# 14-I225-Main.net
KiCad netlist of a schematic drawn in Altium Designer
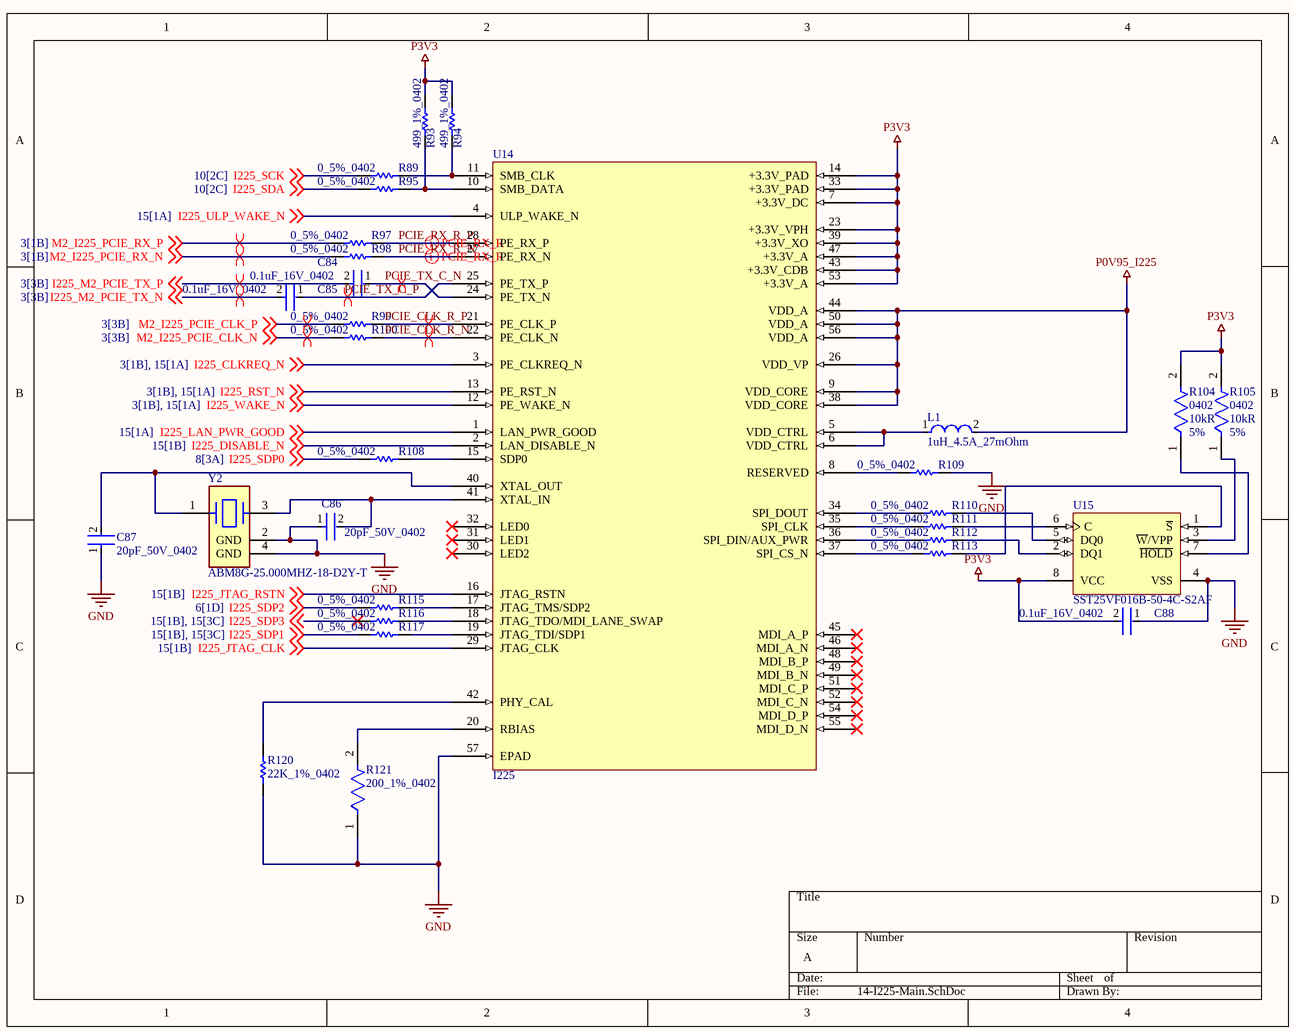
[diagram p0: 14-I225-Main.SchDoc]

(export (version "E")
  (design (tool "Eeschema 10.0.6"))
  (components
    (comp (ref "C84")
      (value "0.1uF_16V_0402")
      (footprint "FP-GRM15-MFG")
      (description "CAP CER 0.1UF 16V X7R 0402")
      (fields (field (name "MANUFACTURER PART NUMBER") "GRM155R71C104KA88D") (field (name "TOLERANCE") "10%"))
      (libsource (lib "Altium Content Vault") (part "236180d848d6139a670b325ea6854c9"))
    )
    (comp (ref "C85")
      (value "0.1uF_16V_0402")
      (footprint "FP-GRM15-MFG")
      (description "CAP CER 0.1UF 16V X7R 0402")
      (fields (field (name "MANUFACTURER PART NUMBER") "GRM155R71C104KA88D") (field (name "TOLERANCE") "10%"))
      (libsource (lib "Altium Content Vault") (part "236180d848d6139a670b325ea6854c9"))
    )
    (comp (ref "C86")
      (value "20pF_50V_0402")
      (footprint "FP-C0402-BB-MFG")
      (description "CAP CER 20PF 50V 5% NP0 0402")
      (fields
        (field (name "MANUFACTURER PART NUMBER") "C0402C200J5GACTU")
        (field (name "OCTOPART") "https://octopart.com/c0402c200j5gactu-kemet-9143900")
      )
      (libsource (lib "Altium Content Vault") (part "b4654b650e69147ec39a6b967a45e02"))
    )
    (comp (ref "C87")
      (value "20pF_50V_0402")
      (footprint "FP-C0402-BB-MFG")
      (description "CAP CER 20PF 50V 5% NP0 0402")
      (fields
        (field (name "MANUFACTURER PART NUMBER") "C0402C200J5GACTU")
        (field (name "OCTOPART") "https://octopart.com/c0402c200j5gactu-kemet-9143900")
      )
      (libsource (lib "Altium Content Vault") (part "b4654b650e69147ec39a6b967a45e02"))
    )
    (comp (ref "C88")
      (value "0.1uF_16V_0402")
      (footprint "FP-GRM15-MFG")
      (description "CAP CER 0.1UF 16V X7R 0402")
      (fields (field (name "MANUFACTURER PART NUMBER") "GRM155R71C104KA88D") (field (name "TOLERANCE") "10%"))
      (libsource (lib "Altium Content Vault") (part "236180d848d6139a670b325ea6854c9"))
    )
    (comp (ref "L1")
      (value "1uH_4.5A_27mOhm")
      (footprint "FP-IHLP-1616BZ-FP_1_8545x-MFG")
      (description "Fixed Inductors Commercial Low DCR Series SMT 1uH 4.5A 27mΩ 20%")
      (fields (field (name "TOLERANCE") "20%"))
      (libsource (lib "Altium Content Vault") (part "725321dda6339637d4d059423bc1c3c"))
    )
    (comp (ref "R89")
      (value "0_5%_0402")
      (footprint "RESC1005X40X25LL10T10")
      (fields (field (name "MANUFACTURER") "KOA Speer") (field (name "PART NUMBER") "RK73Z1ETTP"))
      (libsource (lib "Altium Content Vault") (part "RES"))
    )
    (comp (ref "R93")
      (value "499_1%_0402")
      (footprint "RESC1005X40X25LL05T05")
      (fields (field (name "MANUFACTURER") "Panasonic") (field (name "PART NUMBER") "ERJ-2RKF4990X"))
      (libsource (lib "Altium Content Vault") (part "RES"))
    )
    (comp (ref "R94")
      (value "499_1%_0402")
      (footprint "RESC1005X40X25LL05T05")
      (fields (field (name "MANUFACTURER") "Panasonic") (field (name "PART NUMBER") "ERJ-2RKF4990X"))
      (libsource (lib "Altium Content Vault") (part "RES"))
    )
    (comp (ref "R95")
      (value "0_5%_0402")
      (footprint "RESC1005X40X25LL10T10")
      (fields (field (name "MANUFACTURER") "KOA Speer") (field (name "PART NUMBER") "RK73Z1ETTP"))
      (libsource (lib "Altium Content Vault") (part "RES"))
    )
    (comp (ref "R97")
      (value "0_5%_0402")
      (footprint "RESC1005X40X25LL10T10")
      (fields (field (name "MANUFACTURER") "KOA Speer") (field (name "PART NUMBER") "RK73Z1ETTP"))
      (libsource (lib "Altium Content Vault") (part "RES"))
    )
    (comp (ref "R98")
      (value "0_5%_0402")
      (footprint "RESC1005X40X25LL10T10")
      (fields (field (name "MANUFACTURER") "KOA Speer") (field (name "PART NUMBER") "RK73Z1ETTP"))
      (libsource (lib "Altium Content Vault") (part "RES"))
    )
    (comp (ref "R99")
      (value "0_5%_0402")
      (footprint "RESC1005X40X25LL10T10")
      (fields (field (name "MANUFACTURER") "KOA Speer") (field (name "PART NUMBER") "RK73Z1ETTP"))
      (libsource (lib "Altium Content Vault") (part "RES"))
    )
    (comp (ref "R100")
      (value "0_5%_0402")
      (footprint "RESC1005X40X25LL10T10")
      (fields (field (name "MANUFACTURER") "KOA Speer") (field (name "PART NUMBER") "RK73Z1ETTP"))
      (libsource (lib "Altium Content Vault") (part "RES"))
    )
    (comp (ref "R104")
      (value "CRCW040210K0JNED")
      (footprint "FP-CRCW0402-e3-IPC_B")
      (description "RES Thick Film, 10kΩ, 5%, 0.063W, 200ppm/°C, 0402")
      (fields
        (field (name "CASE/PACKAGE") "0402")
        (field (name "RESISTANCE") "10kR")
        (field (name "TOLERANCE") "5%")
      )
      (libsource (lib "Altium Content Vault") (part "1029c3af85768c4190bb7ad29bc67b5"))
    )
    (comp (ref "R105")
      (value "CRCW040210K0JNED")
      (footprint "FP-CRCW0402-e3-IPC_B")
      (description "RES Thick Film, 10kΩ, 5%, 0.063W, 200ppm/°C, 0402")
      (fields
        (field (name "CASE/PACKAGE") "0402")
        (field (name "RESISTANCE") "10kR")
        (field (name "TOLERANCE") "5%")
      )
      (libsource (lib "Altium Content Vault") (part "1029c3af85768c4190bb7ad29bc67b5"))
    )
    (comp (ref "R108")
      (value "0_5%_0402")
      (footprint "RESC1005X40X25LL10T10")
      (fields (field (name "MANUFACTURER") "KOA Speer") (field (name "PART NUMBER") "RK73Z1ETTP"))
      (libsource (lib "Altium Content Vault") (part "RES"))
    )
    (comp (ref "R109")
      (value "0_5%_0402")
      (footprint "RESC1005X40X25LL10T10")
      (fields (field (name "MANUFACTURER") "KOA Speer") (field (name "PART NUMBER") "RK73Z1ETTP"))
      (libsource (lib "Altium Content Vault") (part "RES"))
    )
    (comp (ref "R110")
      (value "0_5%_0402")
      (footprint "RESC1005X40X25LL10T10")
      (fields (field (name "MANUFACTURER") "KOA Speer") (field (name "PART NUMBER") "RK73Z1ETTP"))
      (libsource (lib "Altium Content Vault") (part "RES"))
    )
    (comp (ref "R111")
      (value "0_5%_0402")
      (footprint "RESC1005X40X25LL10T10")
      (fields (field (name "MANUFACTURER") "KOA Speer") (field (name "PART NUMBER") "RK73Z1ETTP"))
      (libsource (lib "Altium Content Vault") (part "RES"))
    )
    (comp (ref "R112")
      (value "0_5%_0402")
      (footprint "RESC1005X40X25LL10T10")
      (fields (field (name "MANUFACTURER") "KOA Speer") (field (name "PART NUMBER") "RK73Z1ETTP"))
      (libsource (lib "Altium Content Vault") (part "RES"))
    )
    (comp (ref "R113")
      (value "0_5%_0402")
      (footprint "RESC1005X40X25LL10T10")
      (fields (field (name "MANUFACTURER") "KOA Speer") (field (name "PART NUMBER") "RK73Z1ETTP"))
      (libsource (lib "Altium Content Vault") (part "RES"))
    )
    (comp (ref "R115")
      (value "0_5%_0402")
      (footprint "RESC1005X40X25LL10T10")
      (fields (field (name "MANUFACTURER") "KOA Speer") (field (name "PART NUMBER") "RK73Z1ETTP"))
      (libsource (lib "Altium Content Vault") (part "RES"))
    )
    (comp (ref "R116")
      (value "0_5%_0402")
      (footprint "RESC1005X40X25LL10T10")
      (fields (field (name "MANUFACTURER") "KOA Speer") (field (name "PART NUMBER") "RK73Z1ETTP"))
      (libsource (lib "Altium Content Vault") (part "RES"))
    )
    (comp (ref "R117")
      (value "0_5%_0402")
      (footprint "RESC1005X40X25LL10T10")
      (fields (field (name "MANUFACTURER") "KOA Speer") (field (name "PART NUMBER") "RK73Z1ETTP"))
      (libsource (lib "Altium Content Vault") (part "RES"))
    )
    (comp (ref "R120")
      (value "22K_1%_0402")
      (footprint "RESC1005X40X25NL05T05")
      (fields (field (name "PART NUMBER") "CRCW040222K0FKED") (field (name "MANUFACTURER") "Vishay Dale"))
      (libsource (lib "Altium Content Vault") (part "RES"))
    )
    (comp (ref "R121")
      (value "200_1%_0402")
      (footprint "FP-CRCW0402-e3-IPC_C")
      (description "RES Thick Film, 200Ω, 1%, 0.063W, 100ppm/°C, 0402")
      (fields (field (name "TOLERANCE") "1%"))
      (libsource (lib "Altium Content Vault") (part "1029c3af85768c4190bb7ad29bc67b5"))
    )
    (comp (ref "U14") (value "I225") (footprint "I225 QFN56") (libsource (lib "TimeStick_Lib") (part "I225")))
    (comp (ref "U15")
      (value "SST25VF016B-50-4C-S2AF")
      (footprint "MICT-MW-8_N")
      (fields (field (name "VOLTAGE") "2.3V-3.6VÂ") (field (name "MANUFACTURER") "Microchip"))
      (libsource (lib "Altium Content Vault") (part "MICT-M25PX16-VMW-8"))
    )
    (comp (ref "Y2")
      (value "ABM8G-25.000MHZ-18-D2Y-T")
      (footprint "FP-ABM8G-MFG")
      (description "CRYSTAL 25.0000MHZ 18PF SMD")
      (fields
        (field (name "MANUFACTURER") "Abracon")
        (field (name "OCTOPART") "https://octopart.com/abm8g-25.000mhz-18-d2y-t-abracon-12676602")
      )
      (libsource (lib "Altium Content Vault") (part "82af6c543cb7a88a4cbd02a3a01c293"))
    )
  )
  (nets
    (net (code "1") (name "/PCIE_CLK_R_N") (class "Default")
      (node (ref "R100") (pin "2") (pinfunction "2_2") (pintype "passive"))
      (node (ref "U14") (pin "22") (pinfunction "PE_CLK_N_22") (pintype "input"))
    )
    (net (code "2") (name "/PCIE_CLK_R_P") (class "Default")
      (node (ref "R99") (pin "2") (pinfunction "2_2") (pintype "passive"))
      (node (ref "U14") (pin "21") (pinfunction "PE_CLK_P_21") (pintype "input"))
    )
    (net (code "3") (name "/PCIE_RX_R_N") (class "Default")
      (node (ref "R98") (pin "2") (pinfunction "2_2") (pintype "passive"))
      (node (ref "U14") (pin "27") (pinfunction "PE_RX_N_27") (pintype "input"))
    )
    (net (code "4") (name "/PCIE_RX_R_P") (class "Default")
      (node (ref "R97") (pin "2") (pinfunction "2_2") (pintype "passive"))
      (node (ref "U14") (pin "28") (pinfunction "PE_RX_P_28") (pintype "input"))
    )
    (net (code "5") (name "/PCIE_TX_C_N") (class "Default")
      (node (ref "C84") (pin "1") (pinfunction "1_1") (pintype "passive"))
      (node (ref "U14") (pin "24") (pinfunction "PE_TX_N_24") (pintype "input"))
    )
    (net (code "6") (name "/PCIE_TX_C_P") (class "Default")
      (node (ref "C85") (pin "1") (pinfunction "1_1") (pintype "passive"))
      (node (ref "U14") (pin "25") (pinfunction "PE_TX_P_25") (pintype "input"))
    )
    (net (code "7") (name "GND") (class "Default")
      (node (ref "C86") (pin "1") (pinfunction "1_1") (pintype "passive"))
      (node (ref "C87") (pin "1") (pinfunction "1_1") (pintype "passive"))
      (node (ref "C88") (pin "1") (pinfunction "1_1") (pintype "passive"))
      (node (ref "R109") (pin "2") (pinfunction "2_2") (pintype "passive"))
      (node (ref "R120") (pin "1") (pinfunction "1_1") (pintype "passive"))
      (node (ref "R121") (pin "1") (pinfunction "1_1") (pintype "passive"))
      (node (ref "U14") (pin "57") (pinfunction "EPAD_57") (pintype "input"))
      (node (ref "U15") (pin "4") (pinfunction "VSS_4") (pintype "power_in"))
      (node (ref "Y2") (pin "2") (pinfunction "GND_2") (pintype "power_in"))
      (node (ref "Y2") (pin "4") (pinfunction "GND_4") (pintype "power_in"))
    )
    (net (code "8") (name "I225_CLKREQ_N") (class "Default")
      (node (ref "U14") (pin "3") (pinfunction "PE_CLKREQ_N_3") (pintype "input"))
    )
    (net (code "9") (name "I225_DISABLE_N") (class "Default")
      (node (ref "U14") (pin "2") (pinfunction "LAN_DISABLE_N_2") (pintype "input"))
    )
    (net (code "10") (name "I225_JTAG_CLK") (class "Default")
      (node (ref "U14") (pin "29") (pinfunction "JTAG_CLK_29") (pintype "input"))
    )
    (net (code "11") (name "I225_JTAG_RSTN") (class "Default")
      (node (ref "U14") (pin "16") (pinfunction "JTAG_RSTN_16") (pintype "input"))
    )
    (net (code "12") (name "I225_LAN_PWR_GOOD") (class "Default")
      (node (ref "U14") (pin "1") (pinfunction "LAN_PWR_GOOD_1") (pintype "input"))
    )
    (net (code "13") (name "I225_M2_PCIE_TX_N") (class "Default")
      (node (ref "C85") (pin "2") (pinfunction "2_2") (pintype "passive"))
    )
    (net (code "14") (name "I225_M2_PCIE_TX_P") (class "Default")
      (node (ref "C84") (pin "2") (pinfunction "2_2") (pintype "passive"))
    )
    (net (code "15") (name "I225_RST_N") (class "Default")
      (node (ref "U14") (pin "13") (pinfunction "PE_RST_N_13") (pintype "input"))
    )
    (net (code "16") (name "I225_SCK") (class "Default")
      (node (ref "R89") (pin "1") (pinfunction "1_1") (pintype "passive"))
    )
    (net (code "17") (name "I225_SDA") (class "Default")
      (node (ref "R95") (pin "1") (pinfunction "1_1") (pintype "passive"))
    )
    (net (code "18") (name "I225_SDP0") (class "Default")
      (node (ref "R108") (pin "1") (pinfunction "1_1") (pintype "passive"))
    )
    (net (code "19") (name "I225_SDP1") (class "Default")
      (node (ref "R117") (pin "1") (pinfunction "1_1") (pintype "passive"))
    )
    (net (code "20") (name "I225_SDP2") (class "Default")
      (node (ref "R115") (pin "1") (pinfunction "1_1") (pintype "passive"))
    )
    (net (code "21") (name "I225_SDP3") (class "Default")
      (node (ref "R116") (pin "1") (pinfunction "1_1") (pintype "passive"))
    )
    (net (code "22") (name "I225_ULP_WAKE_N") (class "Default")
      (node (ref "U14") (pin "4") (pinfunction "ULP_WAKE_N_4") (pintype "input"))
    )
    (net (code "23") (name "I225_WAKE_N") (class "Default")
      (node (ref "U14") (pin "12") (pinfunction "PE_WAKE_N_12") (pintype "input"))
    )
    (net (code "24") (name "M2_I225_PCIE_CLK_N") (class "Default")
      (node (ref "R100") (pin "1") (pinfunction "1_1") (pintype "passive"))
    )
    (net (code "25") (name "M2_I225_PCIE_CLK_P") (class "Default")
      (node (ref "R99") (pin "1") (pinfunction "1_1") (pintype "passive"))
    )
    (net (code "26") (name "M2_I225_PCIE_RX_N") (class "Default")
      (node (ref "R98") (pin "1") (pinfunction "1_1") (pintype "passive"))
    )
    (net (code "27") (name "M2_I225_PCIE_RX_P") (class "Default")
      (node (ref "R97") (pin "1") (pinfunction "1_1") (pintype "passive"))
    )
    (net (code "28") (name "Net-(L1-Pad1)") (class "Default")
      (node (ref "L1") (pin "1") (pinfunction "1_1") (pintype "passive"))
      (node (ref "U14") (pin "5") (pinfunction "VDD_CTRL_5") (pintype "input"))
      (node (ref "U14") (pin "6") (pinfunction "VDD_CTRL_6") (pintype "input"))
    )
    (net (code "29") (name "Net-(U14-JTAG_TDI{slash}SDP1)") (class "Default")
      (node (ref "R117") (pin "2") (pinfunction "2_2") (pintype "passive"))
      (node (ref "U14") (pin "19") (pinfunction "JTAG_TDI/SDP1_19") (pintype "input"))
    )
    (net (code "30") (name "Net-(U14-JTAG_TDO{slash}MDI_LANE_SWAP)") (class "Default")
      (node (ref "R116") (pin "2") (pinfunction "2_2") (pintype "passive"))
      (node (ref "U14") (pin "18") (pinfunction "JTAG_TDO/MDI_LANE_SWAP_18") (pintype "input"))
    )
    (net (code "31") (name "Net-(U14-JTAG_TMS{slash}SDP2)") (class "Default")
      (node (ref "R115") (pin "2") (pinfunction "2_2") (pintype "passive"))
      (node (ref "U14") (pin "17") (pinfunction "JTAG_TMS/SDP2_17") (pintype "input"))
    )
    (net (code "32") (name "Net-(U14-PHY_CAL)") (class "Default")
      (node (ref "R120") (pin "2") (pinfunction "2_2") (pintype "passive"))
      (node (ref "U14") (pin "42") (pinfunction "PHY_CAL_42") (pintype "input"))
    )
    (net (code "33") (name "Net-(U14-RBIAS)") (class "Default")
      (node (ref "R121") (pin "2") (pinfunction "2_2") (pintype "passive"))
      (node (ref "U14") (pin "20") (pinfunction "RBIAS_20") (pintype "input"))
    )
    (net (code "34") (name "Net-(U14-RESERVED)") (class "Default")
      (node (ref "R109") (pin "1") (pinfunction "1_1") (pintype "passive"))
      (node (ref "U14") (pin "8") (pinfunction "RESERVED_8") (pintype "input"))
    )
    (net (code "35") (name "Net-(U14-SDP0)") (class "Default")
      (node (ref "R108") (pin "2") (pinfunction "2_2") (pintype "passive"))
      (node (ref "U14") (pin "15") (pinfunction "SDP0_15") (pintype "input"))
    )
    (net (code "36") (name "Net-(U14-SMB_CLK)") (class "Default")
      (node (ref "R89") (pin "2") (pinfunction "2_2") (pintype "passive"))
      (node (ref "R94") (pin "1") (pinfunction "1_1") (pintype "passive"))
      (node (ref "U14") (pin "11") (pinfunction "SMB_CLK_11") (pintype "input"))
    )
    (net (code "37") (name "Net-(U14-SMB_DATA)") (class "Default")
      (node (ref "R93") (pin "1") (pinfunction "1_1") (pintype "passive"))
      (node (ref "R95") (pin "2") (pinfunction "2_2") (pintype "passive"))
      (node (ref "U14") (pin "10") (pinfunction "SMB_DATA_10") (pintype "input"))
    )
    (net (code "38") (name "Net-(U14-SPI_CLK)") (class "Default")
      (node (ref "R111") (pin "1") (pinfunction "1_1") (pintype "passive"))
      (node (ref "U14") (pin "35") (pinfunction "SPI_CLK_35") (pintype "input"))
    )
    (net (code "39") (name "Net-(U14-SPI_CS_N)") (class "Default")
      (node (ref "R113") (pin "1") (pinfunction "1_1") (pintype "passive"))
      (node (ref "U14") (pin "37") (pinfunction "SPI_CS_N_37") (pintype "input"))
    )
    (net (code "40") (name "Net-(U14-SPI_DIN{slash}AUX_PWR)") (class "Default")
      (node (ref "R112") (pin "1") (pinfunction "1_1") (pintype "passive"))
      (node (ref "U14") (pin "36") (pinfunction "SPI_DIN/AUX_PWR_36") (pintype "input"))
    )
    (net (code "41") (name "Net-(U14-SPI_DOUT)") (class "Default")
      (node (ref "R110") (pin "1") (pinfunction "1_1") (pintype "passive"))
      (node (ref "U14") (pin "34") (pinfunction "SPI_DOUT_34") (pintype "input"))
    )
    (net (code "42") (name "Net-(U14-XTAL_IN)") (class "Default")
      (node (ref "C86") (pin "2") (pinfunction "2_2") (pintype "passive"))
      (node (ref "U14") (pin "41") (pinfunction "XTAL_IN_41") (pintype "input"))
      (node (ref "Y2") (pin "3") (pinfunction "3_3") (pintype "passive"))
    )
    (net (code "43") (name "Net-(U14-XTAL_OUT)") (class "Default")
      (node (ref "C87") (pin "2") (pinfunction "2_2") (pintype "passive"))
      (node (ref "U14") (pin "40") (pinfunction "XTAL_OUT_40") (pintype "input"))
      (node (ref "Y2") (pin "1") (pinfunction "1_1") (pintype "passive"))
    )
    (net (code "44") (name "Net-(U15-C)") (class "Default")
      (node (ref "R111") (pin "2") (pinfunction "2_2") (pintype "passive"))
      (node (ref "U15") (pin "6") (pinfunction "C_6") (pintype "input"))
    )
    (net (code "45") (name "Net-(U15-DQ0)") (class "Default")
      (node (ref "R110") (pin "2") (pinfunction "2_2") (pintype "passive"))
      (node (ref "U15") (pin "5") (pinfunction "DQ0_5") (pintype "bidirectional"))
    )
    (net (code "46") (name "Net-(U15-DQ1)") (class "Default")
      (node (ref "R112") (pin "2") (pinfunction "2_2") (pintype "passive"))
      (node (ref "U15") (pin "2") (pinfunction "DQ1_2") (pintype "bidirectional"))
    )
    (net (code "47") (name "Net-(U15-~{HOLD})") (class "Default")
      (node (ref "R104") (pin "1") (pinfunction "1_1") (pintype "passive"))
      (node (ref "U15") (pin "7") (pinfunction "~{HOLD}_7") (pintype "input"))
    )
    (net (code "48") (name "Net-(U15-~{S})") (class "Default")
      (node (ref "R113") (pin "2") (pinfunction "2_2") (pintype "passive"))
      (node (ref "U15") (pin "1") (pinfunction "~{S}_1") (pintype "input"))
    )
    (net (code "49") (name "Net-(U15-~{W}{slash}VPP)") (class "Default")
      (node (ref "R105") (pin "1") (pinfunction "1_1") (pintype "passive"))
      (node (ref "U15") (pin "3") (pinfunction "~{W}/VPP_3") (pintype "input"))
    )
    (net (code "50") (name "P0V95_I225") (class "Default")
      (node (ref "L1") (pin "2") (pinfunction "2_2") (pintype "passive"))
      (node (ref "U14") (pin "26") (pinfunction "VDD_VP_26") (pintype "input"))
      (node (ref "U14") (pin "38") (pinfunction "VDD_CORE_38") (pintype "input"))
      (node (ref "U14") (pin "44") (pinfunction "VDD_A_44") (pintype "input"))
      (node (ref "U14") (pin "50") (pinfunction "VDD_A_50") (pintype "input"))
      (node (ref "U14") (pin "56") (pinfunction "VDD_A_56") (pintype "input"))
      (node (ref "U14") (pin "9") (pinfunction "VDD_CORE_9") (pintype "input"))
    )
    (net (code "51") (name "P3V3") (class "Default")
      (node (ref "C88") (pin "2") (pinfunction "2_2") (pintype "passive"))
      (node (ref "R104") (pin "2") (pinfunction "2_2") (pintype "passive"))
      (node (ref "R105") (pin "2") (pinfunction "2_2") (pintype "passive"))
      (node (ref "R93") (pin "2") (pinfunction "2_2") (pintype "passive"))
      (node (ref "R94") (pin "2") (pinfunction "2_2") (pintype "passive"))
      (node (ref "U14") (pin "14") (pinfunction "+3.3V_PAD_14") (pintype "input"))
      (node (ref "U14") (pin "23") (pinfunction "+3.3V_VPH_23") (pintype "input"))
      (node (ref "U14") (pin "33") (pinfunction "+3.3V_PAD_33") (pintype "input"))
      (node (ref "U14") (pin "39") (pinfunction "+3.3V_XO_39") (pintype "input"))
      (node (ref "U14") (pin "43") (pinfunction "+3.3V_CDB_43") (pintype "input"))
      (node (ref "U14") (pin "47") (pinfunction "+3.3V_A_47") (pintype "input"))
      (node (ref "U14") (pin "53") (pinfunction "+3.3V_A_53") (pintype "input"))
      (node (ref "U14") (pin "7") (pinfunction "+3.3V_DC_7") (pintype "input"))
      (node (ref "U15") (pin "8") (pinfunction "VCC_8") (pintype "power_in"))
    )
    (net (code "52") (name "unconnected-(U14-LED0-Pad32)") (class "Default")
      (node (ref "U14") (pin "32") (pinfunction "LED0_32") (pintype "input+no_connect"))
    )
    (net (code "53") (name "unconnected-(U14-LED1-Pad31)") (class "Default")
      (node (ref "U14") (pin "31") (pinfunction "LED1_31") (pintype "input+no_connect"))
    )
    (net (code "54") (name "unconnected-(U14-LED2-Pad30)") (class "Default")
      (node (ref "U14") (pin "30") (pinfunction "LED2_30") (pintype "input+no_connect"))
    )
    (net (code "55") (name "unconnected-(U14-MDI_A_N-Pad46)") (class "Default")
      (node (ref "U14") (pin "46") (pinfunction "MDI_A_N_46") (pintype "input+no_connect"))
    )
    (net (code "56") (name "unconnected-(U14-MDI_A_P-Pad45)") (class "Default")
      (node (ref "U14") (pin "45") (pinfunction "MDI_A_P_45") (pintype "input+no_connect"))
    )
    (net (code "57") (name "unconnected-(U14-MDI_B_N-Pad49)") (class "Default")
      (node (ref "U14") (pin "49") (pinfunction "MDI_B_N_49") (pintype "input+no_connect"))
    )
    (net (code "58") (name "unconnected-(U14-MDI_B_P-Pad48)") (class "Default")
      (node (ref "U14") (pin "48") (pinfunction "MDI_B_P_48") (pintype "input+no_connect"))
    )
    (net (code "59") (name "unconnected-(U14-MDI_C_N-Pad52)") (class "Default")
      (node (ref "U14") (pin "52") (pinfunction "MDI_C_N_52") (pintype "input+no_connect"))
    )
    (net (code "60") (name "unconnected-(U14-MDI_C_P-Pad51)") (class "Default")
      (node (ref "U14") (pin "51") (pinfunction "MDI_C_P_51") (pintype "input+no_connect"))
    )
    (net (code "61") (name "unconnected-(U14-MDI_D_N-Pad55)") (class "Default")
      (node (ref "U14") (pin "55") (pinfunction "MDI_D_N_55") (pintype "input+no_connect"))
    )
    (net (code "62") (name "unconnected-(U14-MDI_D_P-Pad54)") (class "Default")
      (node (ref "U14") (pin "54") (pinfunction "MDI_D_P_54") (pintype "input+no_connect"))
    )
  )
)
